# schema.net
KiCad netlist of a schematic drawn in EAGLE
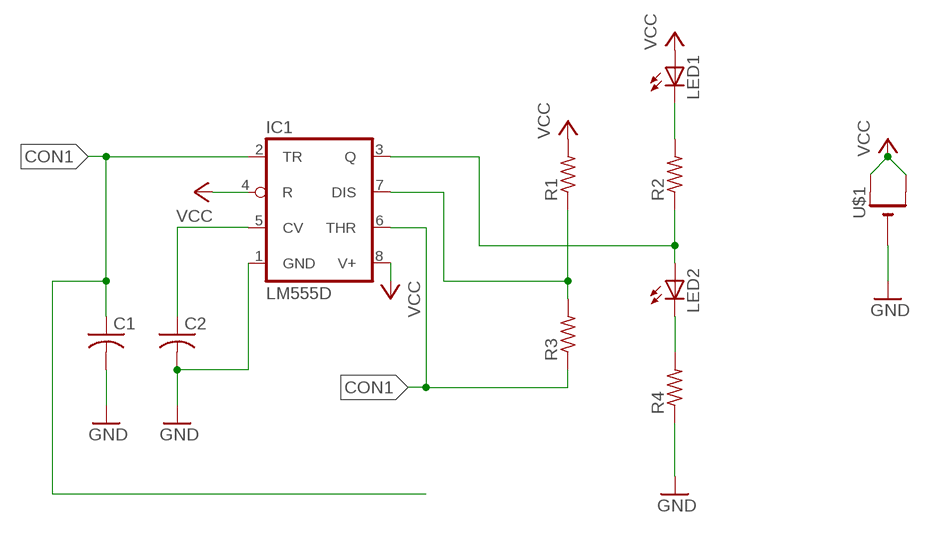
[diagram p0: schematic, sheet 1]

(export (version "E")
  (design (tool "Eeschema 10.0.6"))
  (components
    (comp (ref "C1")
      (value "C-USC0805")
      (footprint "eagle-import:C0805")
      (libsource (lib "eagle-import") (part "C-USC0805"))
    )
    (comp (ref "C2")
      (value "C-USC0805")
      (footprint "eagle-import:C0805")
      (libsource (lib "eagle-import") (part "C-USC0805"))
    )
    (comp (ref "IC1")
      (value "LM555D")
      (footprint "eagle-import:SO08")
      (libsource (lib "eagle-import") (part "555DLM"))
    )
    (comp (ref "LED1")
      (value "LEDCHIPLED_0805")
      (footprint "eagle-import:CHIPLED_0805")
      (libsource (lib "eagle-import") (part "LEDCHIPLED_0805"))
    )
    (comp (ref "LED2")
      (value "LEDCHIPLED_0805")
      (footprint "eagle-import:CHIPLED_0805")
      (libsource (lib "eagle-import") (part "LEDCHIPLED_0805"))
    )
    (comp (ref "R1")
      (value "R-US_R0805")
      (footprint "eagle-import:R0805")
      (libsource (lib "eagle-import") (part "R-US_R0805"))
    )
    (comp (ref "R2")
      (value "R-US_R0805")
      (footprint "eagle-import:R0805")
      (libsource (lib "eagle-import") (part "R-US_R0805"))
    )
    (comp (ref "R3")
      (value "R-US_R0805")
      (footprint "eagle-import:R0805")
      (libsource (lib "eagle-import") (part "R-US_R0805"))
    )
    (comp (ref "R4")
      (value "R-US_R0805")
      (footprint "eagle-import:R0805")
      (libsource (lib "eagle-import") (part "R-US_R0805"))
    )
    (comp (ref "U$1")
      (value "CR1220SMT")
      (footprint "eagle-import:CR1220-SMD")
      (libsource (lib "eagle-import") (part "CR1220SMT"))
    )
  )
  (nets
    (net (code "1") (name "CON1") (class "Default")
      (node (ref "C1") (pin "1") (pinfunction "1_1") (pintype "passive"))
      (node (ref "IC1") (pin "2") (pinfunction "TR_2") (pintype "input"))
      (node (ref "IC1") (pin "6") (pinfunction "THR_6") (pintype "input"))
      (node (ref "R3") (pin "1") (pinfunction "1_1") (pintype "passive"))
    )
    (net (code "2") (name "GND") (class "Default")
      (node (ref "C1") (pin "2") (pinfunction "2_2") (pintype "passive"))
      (node (ref "C2") (pin "2") (pinfunction "2_2") (pintype "passive"))
      (node (ref "IC1") (pin "1") (pinfunction "GND_1") (pintype "power_in"))
      (node (ref "R4") (pin "1") (pinfunction "1_1") (pintype "passive"))
      (node (ref "U$1") (pin "-") (pinfunction "-_-") (pintype "passive"))
    )
    (net (code "3") (name "Net-(IC1-CV)") (class "Default")
      (node (ref "C2") (pin "1") (pinfunction "1_1") (pintype "passive"))
      (node (ref "IC1") (pin "5") (pinfunction "CV_5") (pintype "input"))
    )
    (net (code "4") (name "Net-(IC1-DIS)") (class "Default")
      (node (ref "IC1") (pin "7") (pinfunction "DIS_7") (pintype "input"))
      (node (ref "R1") (pin "1") (pinfunction "1_1") (pintype "passive"))
      (node (ref "R3") (pin "2") (pinfunction "2_2") (pintype "passive"))
    )
    (net (code "5") (name "Net-(IC1-Q)") (class "Default")
      (node (ref "IC1") (pin "3") (pinfunction "Q_3") (pintype "output"))
      (node (ref "LED2") (pin "A") (pinfunction "A_A") (pintype "passive"))
      (node (ref "R2") (pin "1") (pinfunction "1_1") (pintype "passive"))
    )
    (net (code "6") (name "Net-(LED1-PadC)") (class "Default")
      (node (ref "LED1") (pin "C") (pinfunction "C_C") (pintype "passive"))
      (node (ref "R2") (pin "2") (pinfunction "2_2") (pintype "passive"))
    )
    (net (code "7") (name "Net-(LED2-PadC)") (class "Default")
      (node (ref "LED2") (pin "C") (pinfunction "C_C") (pintype "passive"))
      (node (ref "R4") (pin "2") (pinfunction "2_2") (pintype "passive"))
    )
    (net (code "8") (name "VCC") (class "Default")
      (node (ref "IC1") (pin "4") (pinfunction "R_4") (pintype "input"))
      (node (ref "IC1") (pin "8") (pinfunction "V+_8") (pintype "power_in"))
      (node (ref "LED1") (pin "A") (pinfunction "A_A") (pintype "passive"))
      (node (ref "R1") (pin "2") (pinfunction "2_2") (pintype "passive"))
      (node (ref "U$1") (pin "+$1") (pinfunction "+_+$1") (pintype "passive"))
      (node (ref "U$1") (pin "+$2") (pinfunction "+1_+$2") (pintype "passive"))
    )
  )
)
